# LFO-Complex.net
KiCad netlist of a schematic drawn in EAGLE
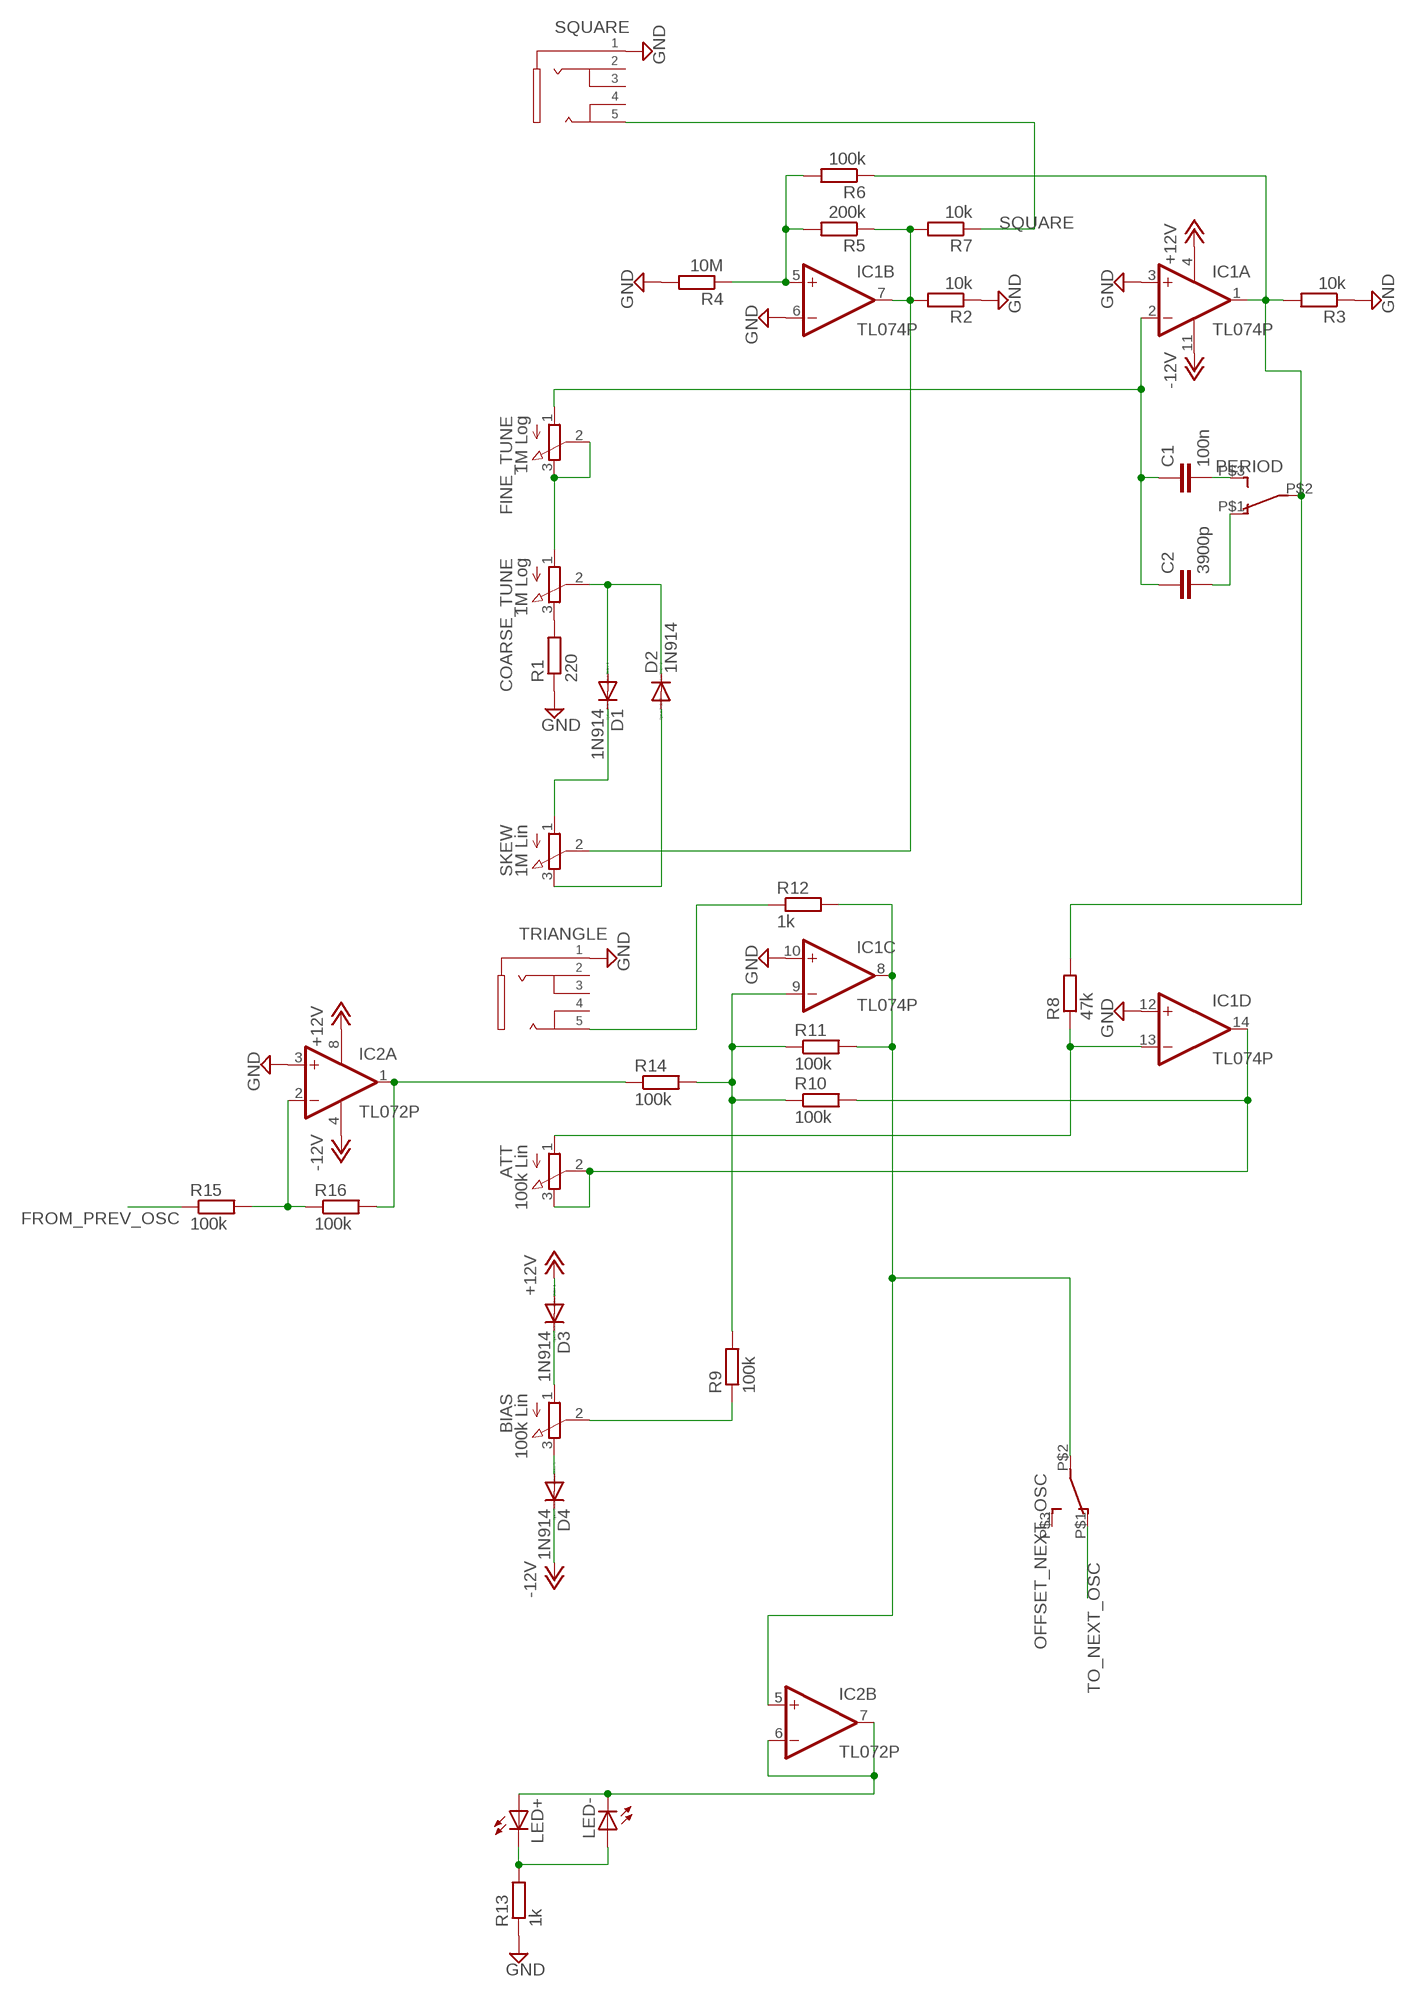
[diagram p0: schematic, sheet 1]

(export (version "E")
  (design (tool "Eeschema 10.0.6"))
  (components
    (comp (ref "ATT")
      (value "100k Lin")
      (footprint "eagle-import:3RP_1610N")
      (libsource (lib "eagle-import") (part "3RP/1610N"))
    )
    (comp (ref "BIAS")
      (value "100k Lin")
      (footprint "eagle-import:3RP_1610N")
      (libsource (lib "eagle-import") (part "3RP/1610N"))
    )
    (comp (ref "C1")
      (value "100n")
      (footprint "eagle-import:C050-025X075")
      (libsource (lib "eagle-import") (part "C-EU050-025X075"))
    )
    (comp (ref "C2")
      (value "3900p")
      (footprint "eagle-import:C050-025X075")
      (libsource (lib "eagle-import") (part "C-EU050-025X075"))
    )
    (comp (ref "COARSE_TUNE")
      (value "1M Log")
      (footprint "eagle-import:3RP_1610N")
      (libsource (lib "eagle-import") (part "3RP/1610N"))
    )
    (comp (ref "D1")
      (value "1N914")
      (footprint "eagle-import:D-6.35")
      (libsource (lib "eagle-import") (part "1N914"))
    )
    (comp (ref "D2")
      (value "1N914")
      (footprint "eagle-import:D-6.35")
      (libsource (lib "eagle-import") (part "1N914"))
    )
    (comp (ref "D3")
      (value "1N914")
      (footprint "eagle-import:D-6.35")
      (libsource (lib "eagle-import") (part "1N914"))
    )
    (comp (ref "D4")
      (value "1N914")
      (footprint "eagle-import:D-6.35")
      (libsource (lib "eagle-import") (part "1N914"))
    )
    (comp (ref "FINE_TUNE")
      (value "1M Log")
      (footprint "eagle-import:3RP_1610N")
      (libsource (lib "eagle-import") (part "3RP/1610N"))
    )
    (comp (ref "IC1")
      (value "TL074P")
      (footprint "eagle-import:DIL14")
      (libsource (lib "eagle-import") (part "TL074P"))
    )
    (comp (ref "IC2")
      (value "TL072P")
      (footprint "eagle-import:DIL08")
      (libsource (lib "eagle-import") (part "TL072P"))
    )
    (comp (ref "LED+")
      (value "LED3MM-NB")
      (footprint "eagle-import:LED3MM")
      (libsource (lib "eagle-import") (part "LED3MM-NB"))
    )
    (comp (ref "LED-")
      (value "LED3MM-NB")
      (footprint "eagle-import:LED3MM")
      (libsource (lib "eagle-import") (part "LED3MM-NB"))
    )
    (comp (ref "OFFSET_NEXT_OSC")
      (value "TOGGLE-NB-MILLED")
      (footprint "eagle-import:TOGGLE-NB-MILLED")
      (libsource (lib "eagle-import") (part "TOGGLE-NB-MILLED"))
    )
    (comp (ref "PERIOD")
      (value "TOGGLE-NB-MILLED")
      (footprint "eagle-import:TOGGLE-NB-MILLED")
      (libsource (lib "eagle-import") (part "TOGGLE-NB-MILLED"))
    )
    (comp (ref "R1")
      (value "220")
      (footprint "eagle-import:0204_7")
      (libsource (lib "eagle-import") (part "BOX-RESISTOR"))
    )
    (comp (ref "R2")
      (value "10k")
      (footprint "eagle-import:0204_7")
      (libsource (lib "eagle-import") (part "BOX-RESISTOR"))
    )
    (comp (ref "R3")
      (value "10k")
      (footprint "eagle-import:0204_7")
      (libsource (lib "eagle-import") (part "BOX-RESISTOR"))
    )
    (comp (ref "R4")
      (value "10M")
      (footprint "eagle-import:0204_7")
      (libsource (lib "eagle-import") (part "BOX-RESISTOR"))
    )
    (comp (ref "R5")
      (value "200k")
      (footprint "eagle-import:0204_7")
      (libsource (lib "eagle-import") (part "BOX-RESISTOR"))
    )
    (comp (ref "R6")
      (value "100k")
      (footprint "eagle-import:0204_7")
      (libsource (lib "eagle-import") (part "BOX-RESISTOR"))
    )
    (comp (ref "R7")
      (value "10k")
      (footprint "eagle-import:0204_7")
      (libsource (lib "eagle-import") (part "BOX-RESISTOR"))
    )
    (comp (ref "R8")
      (value "47k")
      (footprint "eagle-import:0204_7")
      (libsource (lib "eagle-import") (part "BOX-RESISTOR"))
    )
    (comp (ref "R9")
      (value "100k")
      (footprint "eagle-import:0204_7")
      (libsource (lib "eagle-import") (part "BOX-RESISTOR"))
    )
    (comp (ref "R10")
      (value "100k")
      (footprint "eagle-import:0204_7")
      (libsource (lib "eagle-import") (part "BOX-RESISTOR"))
    )
    (comp (ref "R11")
      (value "100k")
      (footprint "eagle-import:0204_7")
      (libsource (lib "eagle-import") (part "BOX-RESISTOR"))
    )
    (comp (ref "R12")
      (value "1k")
      (footprint "eagle-import:0204_7")
      (libsource (lib "eagle-import") (part "BOX-RESISTOR"))
    )
    (comp (ref "R13")
      (value "1k")
      (footprint "eagle-import:0204_7")
      (libsource (lib "eagle-import") (part "BOX-RESISTOR"))
    )
    (comp (ref "R14")
      (value "100k")
      (footprint "eagle-import:0204_7")
      (libsource (lib "eagle-import") (part "BOX-RESISTOR"))
    )
    (comp (ref "R15")
      (value "100k")
      (footprint "eagle-import:0204_7")
      (libsource (lib "eagle-import") (part "BOX-RESISTOR"))
    )
    (comp (ref "R16")
      (value "100k")
      (footprint "eagle-import:0204_7")
      (libsource (lib "eagle-import") (part "BOX-RESISTOR"))
    )
    (comp (ref "SKEW")
      (value "1M Lin")
      (footprint "eagle-import:3RP_1610N")
      (libsource (lib "eagle-import") (part "3RP/1610N"))
    )
    (comp (ref "SQUARE")
      (value "PJ-324MH")
      (footprint "eagle-import:PJ-324MH")
      (libsource (lib "eagle-import") (part "PJ-324MH"))
    )
    (comp (ref "TRIANGLE")
      (value "PJ-324MH")
      (footprint "eagle-import:PJ-324MH")
      (libsource (lib "eagle-import") (part "PJ-324MH"))
    )
  )
  (nets
    (net (code "1") (name "+12V") (class "Default")
      (node (ref "D3") (pin "A") (pinfunction "A_A") (pintype "passive"))
      (node (ref "IC1") (pin "4") (pinfunction "V+_4") (pintype "power_in"))
      (node (ref "IC2") (pin "8") (pinfunction "V+_8") (pintype "power_in"))
    )
    (net (code "2") (name "-12V") (class "Default")
      (node (ref "D4") (pin "C") (pinfunction "C_C") (pintype "passive"))
      (node (ref "IC1") (pin "11") (pinfunction "V-_11") (pintype "power_in"))
      (node (ref "IC2") (pin "4") (pinfunction "V-_4") (pintype "power_in"))
    )
    (net (code "3") (name "/FROM_PREV_OSC") (class "Default")
      (node (ref "R15") (pin "1") (pinfunction "1_1") (pintype "passive"))
    )
    (net (code "4") (name "/SQUARE") (class "Default")
      (node (ref "R7") (pin "1") (pinfunction "1_1") (pintype "passive"))
      (node (ref "SQUARE") (pin "5") (pinfunction "5_5") (pintype "passive"))
    )
    (net (code "5") (name "/TO_NEXT_OSC") (class "Default")
      (node (ref "OFFSET_NEXT_OSC") (pin "P$1") (pinfunction "O_P$1") (pintype "passive"))
    )
    (net (code "6") (name "GND") (class "Default")
      (node (ref "IC1") (pin "10") (pinfunction "+IN_10") (pintype "input"))
      (node (ref "IC1") (pin "12") (pinfunction "+IN_12") (pintype "input"))
      (node (ref "IC1") (pin "3") (pinfunction "+IN_3") (pintype "input"))
      (node (ref "IC1") (pin "6") (pinfunction "-IN_6") (pintype "input"))
      (node (ref "IC2") (pin "3") (pinfunction "+IN_3") (pintype "input"))
      (node (ref "R1") (pin "1") (pinfunction "1_1") (pintype "passive"))
      (node (ref "R13") (pin "1") (pinfunction "1_1") (pintype "passive"))
      (node (ref "R2") (pin "1") (pinfunction "1_1") (pintype "passive"))
      (node (ref "R3") (pin "1") (pinfunction "1_1") (pintype "passive"))
      (node (ref "R4") (pin "2") (pinfunction "2_2") (pintype "passive"))
      (node (ref "SQUARE") (pin "1") (pinfunction "1_1") (pintype "passive"))
      (node (ref "TRIANGLE") (pin "1") (pinfunction "1_1") (pintype "passive"))
    )
    (net (code "7") (name "Net-(ATT-A)") (class "Default")
      (node (ref "ATT") (pin "1") (pinfunction "A_1") (pintype "passive"))
      (node (ref "IC1") (pin "13") (pinfunction "-IN_13") (pintype "input"))
      (node (ref "R8") (pin "1") (pinfunction "1_1") (pintype "passive"))
    )
    (net (code "8") (name "Net-(ATT-E)") (class "Default")
      (node (ref "ATT") (pin "2") (pinfunction "S_2") (pintype "passive"))
      (node (ref "ATT") (pin "3") (pinfunction "E_3") (pintype "passive"))
      (node (ref "IC1") (pin "14") (pinfunction "OUT_14") (pintype "output"))
      (node (ref "R10") (pin "2") (pinfunction "2_2") (pintype "passive"))
    )
    (net (code "9") (name "Net-(BIAS-A)") (class "Default")
      (node (ref "BIAS") (pin "1") (pinfunction "A_1") (pintype "passive"))
      (node (ref "D3") (pin "C") (pinfunction "C_C") (pintype "passive"))
    )
    (net (code "10") (name "Net-(BIAS-E)") (class "Default")
      (node (ref "BIAS") (pin "3") (pinfunction "E_3") (pintype "passive"))
      (node (ref "D4") (pin "A") (pinfunction "A_A") (pintype "passive"))
    )
    (net (code "11") (name "Net-(BIAS-S)") (class "Default")
      (node (ref "BIAS") (pin "2") (pinfunction "S_2") (pintype "passive"))
      (node (ref "R9") (pin "1") (pinfunction "1_1") (pintype "passive"))
    )
    (net (code "12") (name "Net-(COARSE_TUNE-A)") (class "Default")
      (node (ref "COARSE_TUNE") (pin "1") (pinfunction "A_1") (pintype "passive"))
      (node (ref "FINE_TUNE") (pin "2") (pinfunction "S_2") (pintype "passive"))
      (node (ref "FINE_TUNE") (pin "3") (pinfunction "E_3") (pintype "passive"))
    )
    (net (code "13") (name "Net-(COARSE_TUNE-E)") (class "Default")
      (node (ref "COARSE_TUNE") (pin "3") (pinfunction "E_3") (pintype "passive"))
      (node (ref "R1") (pin "2") (pinfunction "2_2") (pintype "passive"))
    )
    (net (code "14") (name "Net-(COARSE_TUNE-S)") (class "Default")
      (node (ref "COARSE_TUNE") (pin "2") (pinfunction "S_2") (pintype "passive"))
      (node (ref "D1") (pin "A") (pinfunction "A_A") (pintype "passive"))
      (node (ref "D2") (pin "C") (pinfunction "C_C") (pintype "passive"))
    )
    (net (code "15") (name "Net-(FINE_TUNE-A)") (class "Default")
      (node (ref "C1") (pin "1") (pinfunction "1_1") (pintype "passive"))
      (node (ref "C2") (pin "1") (pinfunction "1_1") (pintype "passive"))
      (node (ref "FINE_TUNE") (pin "1") (pinfunction "A_1") (pintype "passive"))
      (node (ref "IC1") (pin "2") (pinfunction "-IN_2") (pintype "input"))
    )
    (net (code "16") (name "Net-(IC1A-OUT)") (class "Default")
      (node (ref "IC1") (pin "1") (pinfunction "OUT_1") (pintype "output"))
      (node (ref "PERIOD") (pin "P$2") (pinfunction "P_P$2") (pintype "passive"))
      (node (ref "R3") (pin "2") (pinfunction "2_2") (pintype "passive"))
      (node (ref "R6") (pin "1") (pinfunction "1_1") (pintype "passive"))
      (node (ref "R8") (pin "2") (pinfunction "2_2") (pintype "passive"))
    )
    (net (code "17") (name "Net-(IC1B-+IN)") (class "Default")
      (node (ref "IC1") (pin "5") (pinfunction "+IN_5") (pintype "input"))
      (node (ref "R4") (pin "1") (pinfunction "1_1") (pintype "passive"))
      (node (ref "R5") (pin "2") (pinfunction "2_2") (pintype "passive"))
      (node (ref "R6") (pin "2") (pinfunction "2_2") (pintype "passive"))
    )
    (net (code "18") (name "Net-(IC1B-OUT)") (class "Default")
      (node (ref "IC1") (pin "7") (pinfunction "OUT_7") (pintype "output"))
      (node (ref "R2") (pin "2") (pinfunction "2_2") (pintype "passive"))
      (node (ref "R5") (pin "1") (pinfunction "1_1") (pintype "passive"))
      (node (ref "R7") (pin "2") (pinfunction "2_2") (pintype "passive"))
      (node (ref "SKEW") (pin "2") (pinfunction "S_2") (pintype "passive"))
    )
    (net (code "19") (name "Net-(IC1C--IN)") (class "Default")
      (node (ref "IC1") (pin "9") (pinfunction "-IN_9") (pintype "input"))
      (node (ref "R10") (pin "1") (pinfunction "1_1") (pintype "passive"))
      (node (ref "R11") (pin "1") (pinfunction "1_1") (pintype "passive"))
      (node (ref "R14") (pin "2") (pinfunction "2_2") (pintype "passive"))
      (node (ref "R9") (pin "2") (pinfunction "2_2") (pintype "passive"))
    )
    (net (code "20") (name "Net-(IC1C-OUT)") (class "Default")
      (node (ref "IC1") (pin "8") (pinfunction "OUT_8") (pintype "output"))
      (node (ref "IC2") (pin "5") (pinfunction "+IN_5") (pintype "input"))
      (node (ref "OFFSET_NEXT_OSC") (pin "P$2") (pinfunction "P_P$2") (pintype "passive"))
      (node (ref "R11") (pin "2") (pinfunction "2_2") (pintype "passive"))
      (node (ref "R12") (pin "2") (pinfunction "2_2") (pintype "passive"))
    )
    (net (code "21") (name "Net-(IC2A--IN)") (class "Default")
      (node (ref "IC2") (pin "2") (pinfunction "-IN_2") (pintype "input"))
      (node (ref "R15") (pin "2") (pinfunction "2_2") (pintype "passive"))
      (node (ref "R16") (pin "1") (pinfunction "1_1") (pintype "passive"))
    )
    (net (code "22") (name "Net-(IC2A-OUT)") (class "Default")
      (node (ref "IC2") (pin "1") (pinfunction "OUT_1") (pintype "output"))
      (node (ref "R14") (pin "1") (pinfunction "1_1") (pintype "passive"))
      (node (ref "R16") (pin "2") (pinfunction "2_2") (pintype "passive"))
    )
    (net (code "23") (name "Net-(IC2B--IN)") (class "Default")
      (node (ref "IC2") (pin "6") (pinfunction "-IN_6") (pintype "input"))
      (node (ref "IC2") (pin "7") (pinfunction "OUT_7") (pintype "output"))
      (node (ref "LED+") (pin "A") (pinfunction "A_A") (pintype "passive"))
      (node (ref "LED-") (pin "K") (pinfunction "C_K") (pintype "passive"))
    )
    (net (code "24") (name "Net-(LED+-C)") (class "Default")
      (node (ref "LED+") (pin "K") (pinfunction "C_K") (pintype "passive"))
      (node (ref "LED-") (pin "A") (pinfunction "A_A") (pintype "passive"))
      (node (ref "R13") (pin "2") (pinfunction "2_2") (pintype "passive"))
    )
    (net (code "25") (name "Net-(PERIOD-O)") (class "Default")
      (node (ref "C2") (pin "2") (pinfunction "2_2") (pintype "passive"))
      (node (ref "PERIOD") (pin "P$1") (pinfunction "O_P$1") (pintype "passive"))
    )
    (net (code "26") (name "Net-(PERIOD-S)") (class "Default")
      (node (ref "C1") (pin "2") (pinfunction "2_2") (pintype "passive"))
      (node (ref "PERIOD") (pin "P$3") (pinfunction "S_P$3") (pintype "passive"))
    )
    (net (code "27") (name "Net-(R12-Pad1)") (class "Default")
      (node (ref "R12") (pin "1") (pinfunction "1_1") (pintype "passive"))
      (node (ref "TRIANGLE") (pin "5") (pinfunction "5_5") (pintype "passive"))
    )
    (net (code "28") (name "Net-(SKEW-A)") (class "Default")
      (node (ref "D1") (pin "C") (pinfunction "C_C") (pintype "passive"))
      (node (ref "SKEW") (pin "1") (pinfunction "A_1") (pintype "passive"))
    )
    (net (code "29") (name "Net-(SKEW-E)") (class "Default")
      (node (ref "D2") (pin "A") (pinfunction "A_A") (pintype "passive"))
      (node (ref "SKEW") (pin "3") (pinfunction "E_3") (pintype "passive"))
    )
    (net (code "30") (name "unconnected-(OFFSET_NEXT_OSC-S-PadP$3)") (class "Default")
      (node (ref "OFFSET_NEXT_OSC") (pin "P$3") (pinfunction "S_P$3") (pintype "passive"))
    )
    (net (code "31") (name "unconnected-(SQUARE-Pad2)") (class "Default")
      (node (ref "SQUARE") (pin "2") (pinfunction "2_2") (pintype "passive"))
    )
    (net (code "32") (name "unconnected-(SQUARE-Pad3)") (class "Default")
      (node (ref "SQUARE") (pin "3") (pinfunction "3_3") (pintype "passive"))
    )
    (net (code "33") (name "unconnected-(SQUARE-Pad4)") (class "Default")
      (node (ref "SQUARE") (pin "4") (pinfunction "4_4") (pintype "passive"))
    )
    (net (code "34") (name "unconnected-(TRIANGLE-Pad2)") (class "Default")
      (node (ref "TRIANGLE") (pin "2") (pinfunction "2_2") (pintype "passive"))
    )
    (net (code "35") (name "unconnected-(TRIANGLE-Pad3)") (class "Default")
      (node (ref "TRIANGLE") (pin "3") (pinfunction "3_3") (pintype "passive"))
    )
    (net (code "36") (name "unconnected-(TRIANGLE-Pad4)") (class "Default")
      (node (ref "TRIANGLE") (pin "4") (pinfunction "4_4") (pintype "passive"))
    )
  )
)
